# power-shield-v210.net
KiCad netlist of a schematic drawn in EAGLE
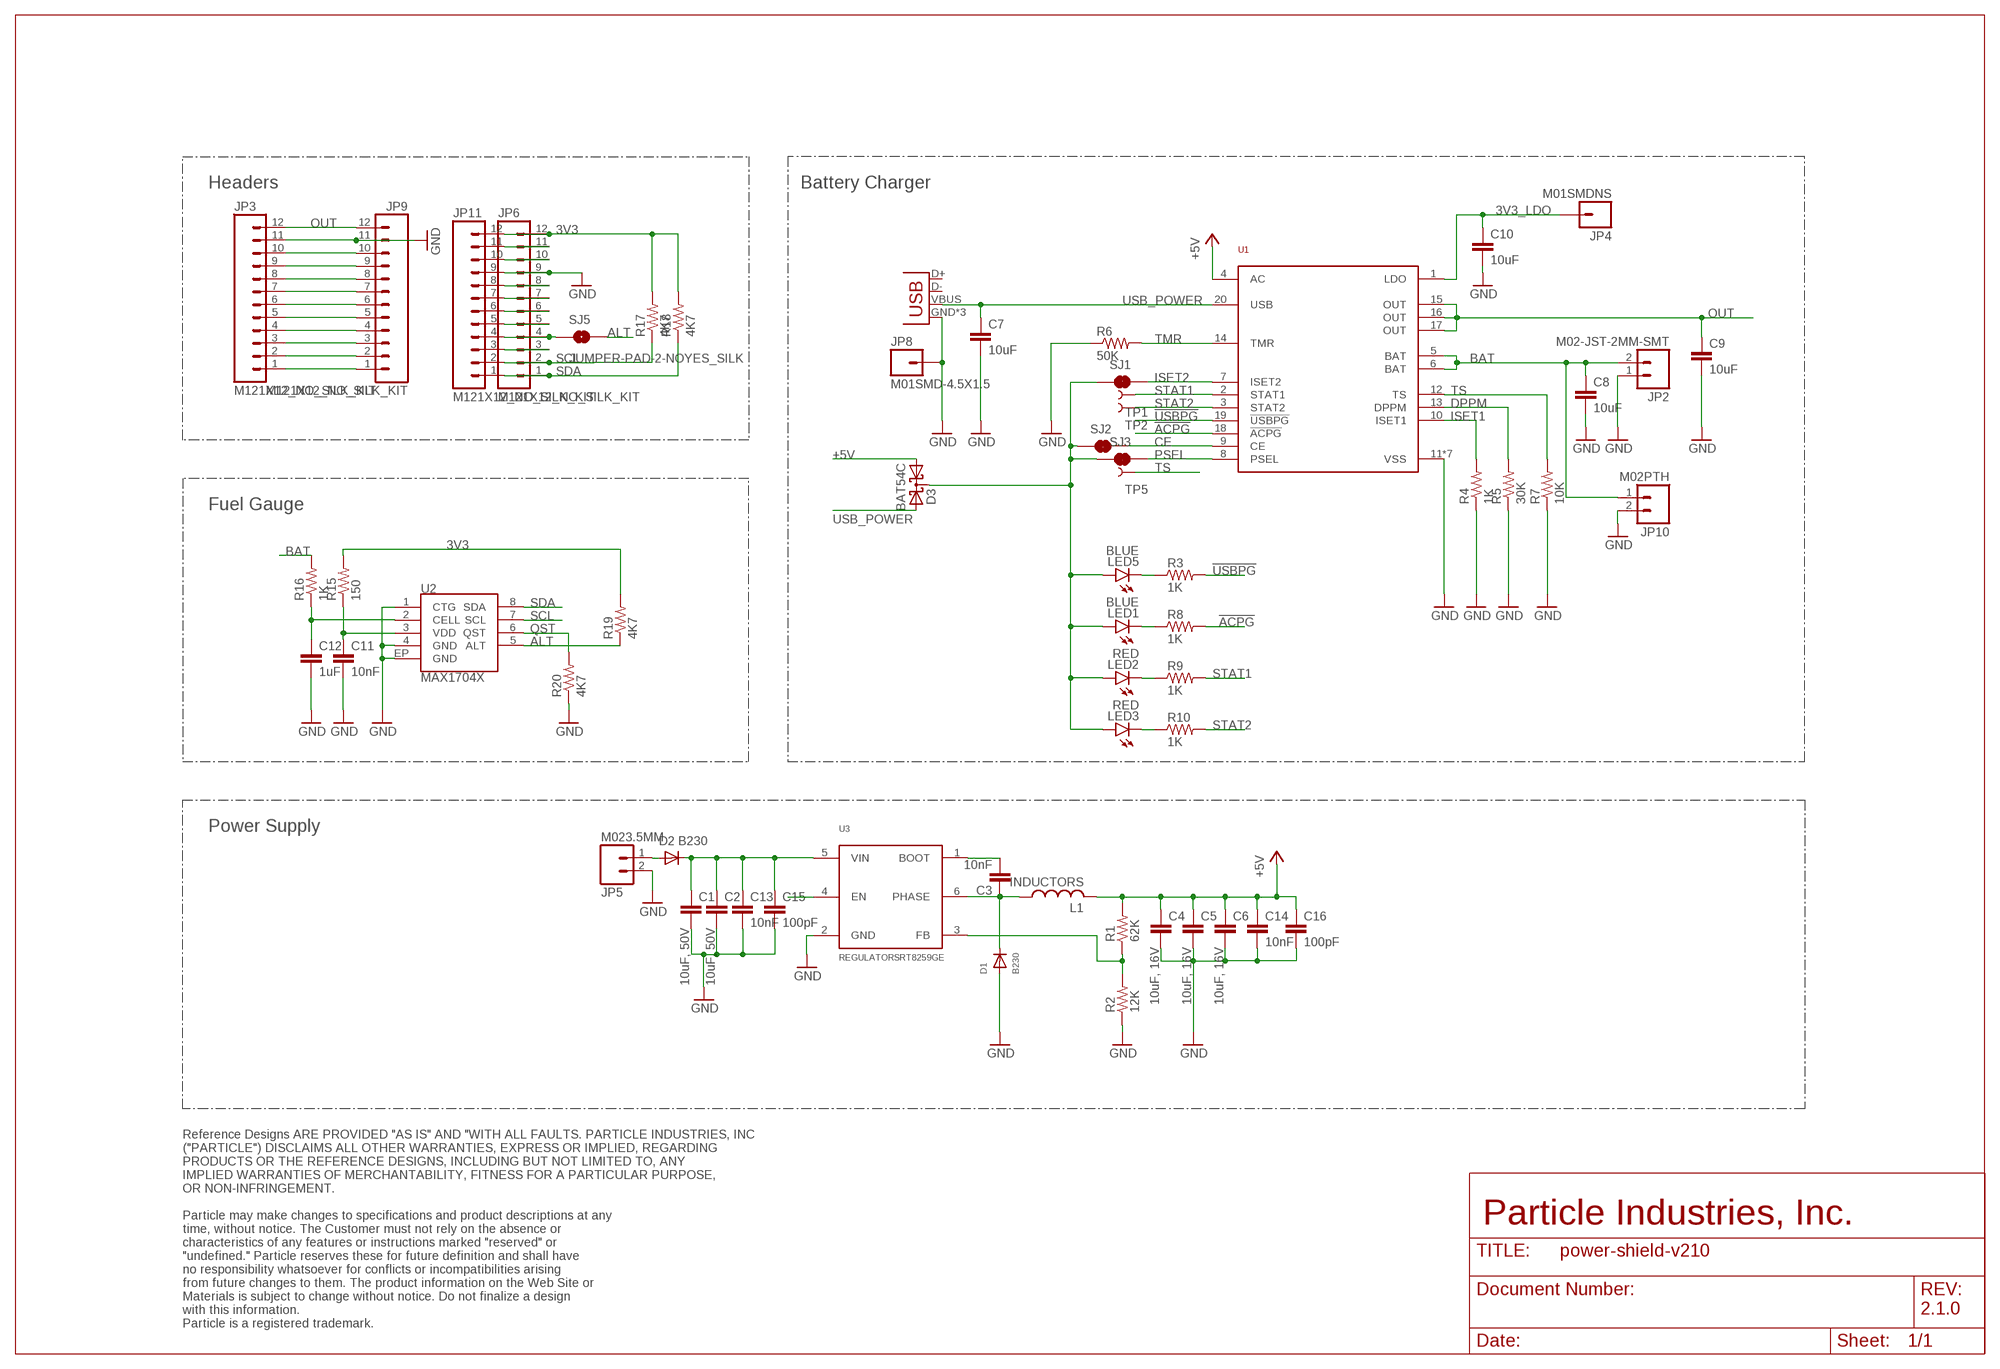
[diagram p0: schematic, sheet 1]

(export (version "E")
  (design (tool "Eeschema 10.0.6"))
  (components
    (comp (ref "C1")
      (value "10uF, 50V")
      (footprint "eagle-import:1206")
      (libsource (lib "eagle-import") (part "CAP1206"))
    )
    (comp (ref "C2")
      (value "10uF, 50V")
      (footprint "eagle-import:1206")
      (libsource (lib "eagle-import") (part "CAP1206"))
    )
    (comp (ref "C3")
      (value "10nF")
      (footprint "eagle-import:0402-CAP")
      (libsource (lib "eagle-import") (part "CAP0402-CAP"))
    )
    (comp (ref "C4")
      (value "10uF, 16V")
      (footprint "eagle-import:1206")
      (libsource (lib "eagle-import") (part "CAP1206"))
    )
    (comp (ref "C5")
      (value "10uF, 16V")
      (footprint "eagle-import:1206")
      (libsource (lib "eagle-import") (part "CAP1206"))
    )
    (comp (ref "C6")
      (value "10uF, 16V")
      (footprint "eagle-import:1206")
      (libsource (lib "eagle-import") (part "CAP1206"))
    )
    (comp (ref "C7")
      (value "10uF")
      (footprint "eagle-import:0603-CAP")
      (libsource (lib "eagle-import") (part "CAP0603-CAP"))
    )
    (comp (ref "C8")
      (value "10uF")
      (footprint "eagle-import:0603-CAP")
      (libsource (lib "eagle-import") (part "CAP0603-CAP"))
    )
    (comp (ref "C9")
      (value "10uF")
      (footprint "eagle-import:0603-CAP")
      (libsource (lib "eagle-import") (part "CAP0603-CAP"))
    )
    (comp (ref "C10")
      (value "10uF")
      (footprint "eagle-import:0603-CAP")
      (libsource (lib "eagle-import") (part "CAP0603-CAP"))
    )
    (comp (ref "C11")
      (value "10nF")
      (footprint "eagle-import:0402-CAP")
      (libsource (lib "eagle-import") (part "CAP0402-CAP"))
    )
    (comp (ref "C12")
      (value "1uF")
      (footprint "eagle-import:0402-CAP")
      (libsource (lib "eagle-import") (part "CAP0402-CAP"))
    )
    (comp (ref "C13")
      (value "10nF")
      (footprint "eagle-import:0402-CAP")
      (libsource (lib "eagle-import") (part "CAP0402-CAP"))
    )
    (comp (ref "C14")
      (value "10nF")
      (footprint "eagle-import:0402-CAP")
      (libsource (lib "eagle-import") (part "CAP0402-CAP"))
    )
    (comp (ref "C15")
      (value "100pF")
      (footprint "eagle-import:0402-CAP")
      (libsource (lib "eagle-import") (part "CAP0402-CAP"))
    )
    (comp (ref "C16")
      (value "100pF")
      (footprint "eagle-import:0402-CAP")
      (libsource (lib "eagle-import") (part "CAP0402-CAP"))
    )
    (comp (ref "D1")
      (value "B230")
      (footprint "eagle-import:SMADIODE")
      (libsource (lib "eagle-import") (part "DIODESMA"))
    )
    (comp (ref "D2")
      (value "B230")
      (footprint "eagle-import:SMADIODE")
      (libsource (lib "eagle-import") (part "DIODESMA"))
    )
    (comp (ref "D3")
      (value "BAT54C")
      (footprint "eagle-import:SOT23")
      (libsource (lib "eagle-import") (part "BAT54C"))
    )
    (comp (ref "JP1")
      (value "USBUSB-MICROB-SLOT-HOLE")
      (footprint "eagle-import:USB-MICROB-SLOT-HOLE")
      (libsource (lib "eagle-import") (part "USBUSB-MICROB-SLOT-HOLE"))
    )
    (comp (ref "JP2")
      (value "M02-JST-2MM-SMT")
      (footprint "eagle-import:JST-2-SMD")
      (libsource (lib "eagle-import") (part "M02-JST-2MM-SMT"))
    )
    (comp (ref "JP3")
      (value "M121X12_NO_SILK_KIT")
      (footprint "eagle-import:1X12_NO_SILK_KIT")
      (libsource (lib "eagle-import") (part "M121X12_NO_SILK_KIT"))
    )
    (comp (ref "JP4")
      (value "M01SMDNS")
      (footprint "eagle-import:1X01NS")
      (libsource (lib "eagle-import") (part "M01SMDNS"))
    )
    (comp (ref "JP5")
      (value "M023.5MM")
      (footprint "eagle-import:SCREWTERMINAL-3.5MM-2")
      (libsource (lib "eagle-import") (part "M023.5MM"))
    )
    (comp (ref "JP6")
      (value "M121X12_NO_SILK_KIT")
      (footprint "eagle-import:1X12_NO_SILK_KIT")
      (libsource (lib "eagle-import") (part "M121X12_NO_SILK_KIT"))
    )
    (comp (ref "JP8")
      (value "M01SMD-4.5X1.5")
      (footprint "eagle-import:PAD-1.5X4.5")
      (libsource (lib "eagle-import") (part "M01SMD-4.5X1.5"))
    )
    (comp (ref "JP9")
      (value "M121X12_NO_SILK_KIT")
      (footprint "eagle-import:1X12_NO_SILK_KIT")
      (libsource (lib "eagle-import") (part "M121X12_NO_SILK_KIT"))
    )
    (comp (ref "JP10")
      (value "M02PTH")
      (footprint "eagle-import:1X02")
      (libsource (lib "eagle-import") (part "M02PTH"))
    )
    (comp (ref "JP11")
      (value "M121X12_NO_SILK_KIT")
      (footprint "eagle-import:1X12_NO_SILK_KIT")
      (libsource (lib "eagle-import") (part "M121X12_NO_SILK_KIT"))
    )
    (comp (ref "L1")
      (value "INDUCTORS")
      (footprint "eagle-import:NR8040T6R8N")
      (libsource (lib "eagle-import") (part "INDUCTORS"))
    )
    (comp (ref "LED1")
      (value "BLUE")
      (footprint "eagle-import:LED-0603")
      (libsource (lib "eagle-import") (part "LED0603"))
    )
    (comp (ref "LED2")
      (value "RED")
      (footprint "eagle-import:LED-0603")
      (libsource (lib "eagle-import") (part "LED0603"))
    )
    (comp (ref "LED3")
      (value "RED")
      (footprint "eagle-import:LED-0603")
      (libsource (lib "eagle-import") (part "LED0603"))
    )
    (comp (ref "LED5")
      (value "BLUE")
      (footprint "eagle-import:LED-0603")
      (libsource (lib "eagle-import") (part "LED0603"))
    )
    (comp (ref "R1")
      (value "62K")
      (footprint "eagle-import:0603-RES")
      (libsource (lib "eagle-import") (part "RESISTOR0603-RES"))
    )
    (comp (ref "R2")
      (value "12K")
      (footprint "eagle-import:0603-RES")
      (libsource (lib "eagle-import") (part "RESISTOR0603-RES"))
    )
    (comp (ref "R3")
      (value "1K")
      (footprint "eagle-import:0402-RES")
      (libsource (lib "eagle-import") (part "RESISTOR0402-RES"))
    )
    (comp (ref "R4")
      (value "1K")
      (footprint "eagle-import:0402-RES")
      (libsource (lib "eagle-import") (part "RESISTOR0402-RES"))
    )
    (comp (ref "R5")
      (value "30K")
      (footprint "eagle-import:0402-RES")
      (libsource (lib "eagle-import") (part "RESISTOR0402-RES"))
    )
    (comp (ref "R6")
      (value "50K")
      (footprint "eagle-import:0402-RES")
      (libsource (lib "eagle-import") (part "RESISTOR0402-RES"))
    )
    (comp (ref "R7")
      (value "10K")
      (footprint "eagle-import:0402-RES")
      (libsource (lib "eagle-import") (part "RESISTOR0402-RES"))
    )
    (comp (ref "R8")
      (value "1K")
      (footprint "eagle-import:0402-RES")
      (libsource (lib "eagle-import") (part "RESISTOR0402-RES"))
    )
    (comp (ref "R9")
      (value "1K")
      (footprint "eagle-import:0402-RES")
      (libsource (lib "eagle-import") (part "RESISTOR0402-RES"))
    )
    (comp (ref "R10")
      (value "1K")
      (footprint "eagle-import:0402-RES")
      (libsource (lib "eagle-import") (part "RESISTOR0402-RES"))
    )
    (comp (ref "R15")
      (value "150")
      (footprint "eagle-import:0603-RES")
      (libsource (lib "eagle-import") (part "RESISTOR0603-RES"))
    )
    (comp (ref "R16")
      (value "1K")
      (footprint "eagle-import:0603-RES")
      (libsource (lib "eagle-import") (part "RESISTOR0603-RES"))
    )
    (comp (ref "R17")
      (value "4K7")
      (footprint "eagle-import:0402-RES")
      (libsource (lib "eagle-import") (part "RESISTOR0402-RES"))
    )
    (comp (ref "R18")
      (value "4K7")
      (footprint "eagle-import:0402-RES")
      (libsource (lib "eagle-import") (part "RESISTOR0402-RES"))
    )
    (comp (ref "R19")
      (value "4K7")
      (footprint "eagle-import:0402-RES")
      (libsource (lib "eagle-import") (part "RESISTOR0402-RES"))
    )
    (comp (ref "R20")
      (value "4K7")
      (footprint "eagle-import:0402-RES")
      (libsource (lib "eagle-import") (part "RESISTOR0402-RES"))
    )
    (comp (ref "SJ1")
      (value "JUMPER-PAD-2-NC_BY_TRACE")
      (footprint "eagle-import:PAD-JUMPER-2-NC_BY_TRACE_YES_SILK")
      (libsource (lib "eagle-import") (part "JUMPER-PAD-2-NC_BY_TRACE"))
    )
    (comp (ref "SJ2")
      (value "JUMPER-PAD-2-NC_BY_TRACE")
      (footprint "eagle-import:PAD-JUMPER-2-NC_BY_TRACE_YES_SILK")
      (libsource (lib "eagle-import") (part "JUMPER-PAD-2-NC_BY_TRACE"))
    )
    (comp (ref "SJ3")
      (value "JUMPER-PAD-2-NC_BY_TRACE")
      (footprint "eagle-import:PAD-JUMPER-2-NC_BY_TRACE_YES_SILK")
      (libsource (lib "eagle-import") (part "JUMPER-PAD-2-NC_BY_TRACE"))
    )
    (comp (ref "SJ5")
      (value "JUMPER-PAD-2-NOYES_SILK")
      (footprint "eagle-import:PAD-JUMPER-2-NO_YES_SILK")
      (libsource (lib "eagle-import") (part "JUMPER-PAD-2-NOYES_SILK"))
    )
    (comp (ref "TP1")
      (value "TEST-POINT3")
      (footprint "eagle-import:PAD.03X.03")
      (libsource (lib "eagle-import") (part "TEST-POINT3"))
    )
    (comp (ref "TP2")
      (value "TEST-POINT3")
      (footprint "eagle-import:PAD.03X.03")
      (libsource (lib "eagle-import") (part "TEST-POINT3"))
    )
    (comp (ref "TP5")
      (value "TEST-POINT3")
      (footprint "eagle-import:PAD.03X.03")
      (libsource (lib "eagle-import") (part "TEST-POINT3"))
    )
    (comp (ref "U1")
      (value "BQ24030BQ24030")
      (footprint "eagle-import:R-PVQFN-N20")
      (libsource (lib "eagle-import") (part "BQ24030BQ24030"))
    )
    (comp (ref "U2")
      (value "MAX1704X")
      (footprint "eagle-import:TDFN-8")
      (libsource (lib "eagle-import") (part "MAX1704X"))
    )
    (comp (ref "U3")
      (value "REGULATORSRT8259GE")
      (footprint "eagle-import:SOT23-6")
      (libsource (lib "eagle-import") (part "REGULATORSRT8259GE"))
    )
  )
  (nets
    (net (code "1") (name "+5V") (class "Default")
      (node (ref "C14") (pin "1") (pinfunction "1_1") (pintype "passive"))
      (node (ref "C16") (pin "1") (pinfunction "1_1") (pintype "passive"))
      (node (ref "C4") (pin "1") (pinfunction "1_1") (pintype "passive"))
      (node (ref "C5") (pin "1") (pinfunction "1_1") (pintype "passive"))
      (node (ref "C6") (pin "1") (pinfunction "1_1") (pintype "passive"))
      (node (ref "D3") (pin "1") (pinfunction "A1_1") (pintype "passive"))
      (node (ref "L1") (pin "P$2") (pinfunction "2_P$2") (pintype "passive"))
      (node (ref "R1") (pin "2") (pinfunction "2_2") (pintype "passive"))
      (node (ref "U1") (pin "4") (pinfunction "AC_4") (pintype "power_in"))
    )
    (net (code "2") (name "/3V3") (class "Default")
      (node (ref "JP11") (pin "12") (pinfunction "12_12") (pintype "passive"))
      (node (ref "JP6") (pin "12") (pinfunction "12_12") (pintype "passive"))
      (node (ref "R15") (pin "2") (pinfunction "2_2") (pintype "passive"))
      (node (ref "R17") (pin "2") (pinfunction "2_2") (pintype "passive"))
      (node (ref "R18") (pin "2") (pinfunction "2_2") (pintype "passive"))
      (node (ref "R19") (pin "2") (pinfunction "2_2") (pintype "passive"))
    )
    (net (code "3") (name "/3V3_LDO") (class "Default")
      (node (ref "C10") (pin "1") (pinfunction "1_1") (pintype "passive"))
      (node (ref "JP4") (pin "1") (pinfunction "1_1") (pintype "passive"))
      (node (ref "U1") (pin "1") (pinfunction "LDO_1") (pintype "output"))
    )
    (net (code "4") (name "/ALT") (class "Default")
      (node (ref "R19") (pin "1") (pinfunction "1_1") (pintype "passive"))
      (node (ref "SJ5") (pin "2") (pinfunction "2_2") (pintype "passive"))
      (node (ref "U2") (pin "5") (pinfunction "ALT_5") (pintype "bidirectional"))
    )
    (net (code "5") (name "/BAT") (class "Default")
      (node (ref "C8") (pin "1") (pinfunction "1_1") (pintype "passive"))
      (node (ref "JP10") (pin "1") (pinfunction "1_1") (pintype "passive"))
      (node (ref "JP2") (pin "2") (pinfunction "1_2") (pintype "passive"))
      (node (ref "R16") (pin "2") (pinfunction "2_2") (pintype "passive"))
      (node (ref "U1") (pin "5") (pinfunction "BAT_5") (pintype "output"))
      (node (ref "U1") (pin "6") (pinfunction "BAT_6") (pintype "output"))
    )
    (net (code "6") (name "/CE") (class "Default")
      (node (ref "SJ2") (pin "2") (pinfunction "2_2") (pintype "passive"))
      (node (ref "U1") (pin "9") (pinfunction "CE_9") (pintype "input"))
    )
    (net (code "7") (name "/DPPM") (class "Default")
      (node (ref "R5") (pin "2") (pinfunction "2_2") (pintype "passive"))
      (node (ref "U1") (pin "13") (pinfunction "DPPM_13") (pintype "bidirectional"))
    )
    (net (code "8") (name "/ISET1") (class "Default")
      (node (ref "R4") (pin "2") (pinfunction "2_2") (pintype "passive"))
      (node (ref "U1") (pin "10") (pinfunction "ISET1_10") (pintype "bidirectional"))
    )
    (net (code "9") (name "/ISET2") (class "Default")
      (node (ref "SJ1") (pin "2") (pinfunction "2_2") (pintype "passive"))
      (node (ref "U1") (pin "7") (pinfunction "ISET2_7") (pintype "input"))
    )
    (net (code "10") (name "/OUT") (class "Default")
      (node (ref "C9") (pin "1") (pinfunction "1_1") (pintype "passive"))
      (node (ref "JP3") (pin "12") (pinfunction "12_12") (pintype "passive"))
      (node (ref "JP9") (pin "12") (pinfunction "12_12") (pintype "passive"))
      (node (ref "U1") (pin "15") (pinfunction "OUT_15") (pintype "output"))
      (node (ref "U1") (pin "16") (pinfunction "OUT_16") (pintype "output"))
      (node (ref "U1") (pin "17") (pinfunction "OUT_17") (pintype "output"))
    )
    (net (code "11") (name "/PSEL") (class "Default")
      (node (ref "SJ3") (pin "2") (pinfunction "2_2") (pintype "passive"))
      (node (ref "U1") (pin "8") (pinfunction "PSEL_8") (pintype "input"))
    )
    (net (code "12") (name "/QST") (class "Default")
      (node (ref "R20") (pin "2") (pinfunction "2_2") (pintype "passive"))
      (node (ref "U2") (pin "6") (pinfunction "QST_6") (pintype "bidirectional"))
    )
    (net (code "13") (name "/SCL") (class "Default")
      (node (ref "JP11") (pin "2") (pinfunction "2_2") (pintype "passive"))
      (node (ref "JP6") (pin "2") (pinfunction "2_2") (pintype "passive"))
      (node (ref "R17") (pin "1") (pinfunction "1_1") (pintype "passive"))
      (node (ref "U2") (pin "7") (pinfunction "SCL_7") (pintype "bidirectional"))
    )
    (net (code "14") (name "/SDA") (class "Default")
      (node (ref "JP11") (pin "1") (pinfunction "1_1") (pintype "passive"))
      (node (ref "JP6") (pin "1") (pinfunction "1_1") (pintype "passive"))
      (node (ref "R18") (pin "1") (pinfunction "1_1") (pintype "passive"))
      (node (ref "U2") (pin "8") (pinfunction "SDA_8") (pintype "bidirectional"))
    )
    (net (code "15") (name "/STAT1") (class "Default")
      (node (ref "R9") (pin "2") (pinfunction "2_2") (pintype "passive"))
      (node (ref "TP1") (pin "P$1") (pinfunction "1_P$1") (pintype "bidirectional"))
      (node (ref "U1") (pin "2") (pinfunction "STAT1_2") (pintype "output"))
    )
    (net (code "16") (name "/STAT2") (class "Default")
      (node (ref "R10") (pin "2") (pinfunction "2_2") (pintype "passive"))
      (node (ref "TP2") (pin "P$1") (pinfunction "1_P$1") (pintype "bidirectional"))
      (node (ref "U1") (pin "3") (pinfunction "STAT2_3") (pintype "output"))
    )
    (net (code "17") (name "/TMR") (class "Default")
      (node (ref "R6") (pin "2") (pinfunction "2_2") (pintype "passive"))
      (node (ref "U1") (pin "14") (pinfunction "TMR_14") (pintype "power_in"))
    )
    (net (code "18") (name "/TS") (class "Default")
      (node (ref "R7") (pin "2") (pinfunction "2_2") (pintype "passive"))
      (node (ref "TP5") (pin "P$1") (pinfunction "1_P$1") (pintype "bidirectional"))
      (node (ref "U1") (pin "12") (pinfunction "TS_12") (pintype "bidirectional"))
    )
    (net (code "19") (name "/USB_POWER") (class "Default")
      (node (ref "C7") (pin "1") (pinfunction "1_1") (pintype "passive"))
      (node (ref "D3") (pin "2") (pinfunction "A2_2") (pintype "passive"))
      (node (ref "JP1") (pin "VBUS") (pinfunction "VBUS_VBUS") (pintype "bidirectional"))
      (node (ref "U1") (pin "20") (pinfunction "USB_20") (pintype "power_in"))
    )
    (net (code "20") (name "/~{ACPG}") (class "Default")
      (node (ref "R8") (pin "2") (pinfunction "2_2") (pintype "passive"))
      (node (ref "U1") (pin "18") (pinfunction "~{ACPG}_18") (pintype "input"))
    )
    (net (code "21") (name "/~{USBPG}") (class "Default")
      (node (ref "R3") (pin "2") (pinfunction "2_2") (pintype "passive"))
      (node (ref "U1") (pin "19") (pinfunction "~{USBPG}_19") (pintype "input"))
    )
    (net (code "22") (name "GND") (class "Default")
      (node (ref "C1") (pin "2") (pinfunction "2_2") (pintype "passive"))
      (node (ref "C10") (pin "2") (pinfunction "2_2") (pintype "passive"))
      (node (ref "C11") (pin "2") (pinfunction "2_2") (pintype "passive"))
      (node (ref "C12") (pin "2") (pinfunction "2_2") (pintype "passive"))
      (node (ref "C13") (pin "2") (pinfunction "2_2") (pintype "passive"))
      (node (ref "C14") (pin "2") (pinfunction "2_2") (pintype "passive"))
      (node (ref "C15") (pin "2") (pinfunction "2_2") (pintype "passive"))
      (node (ref "C16") (pin "2") (pinfunction "2_2") (pintype "passive"))
      (node (ref "C2") (pin "2") (pinfunction "2_2") (pintype "passive"))
      (node (ref "C4") (pin "2") (pinfunction "2_2") (pintype "passive"))
      (node (ref "C5") (pin "2") (pinfunction "2_2") (pintype "passive"))
      (node (ref "C6") (pin "2") (pinfunction "2_2") (pintype "passive"))
      (node (ref "C7") (pin "2") (pinfunction "2_2") (pintype "passive"))
      (node (ref "C8") (pin "2") (pinfunction "2_2") (pintype "passive"))
      (node (ref "C9") (pin "2") (pinfunction "2_2") (pintype "passive"))
      (node (ref "D1") (pin "A") (pinfunction "A_A") (pintype "passive"))
      (node (ref "JP1") (pin "GND") (pinfunction "GND_GND") (pintype "bidirectional"))
      (node (ref "JP1") (pin "MT1") (pinfunction "GND_MT1") (pintype "bidirectional"))
      (node (ref "JP1") (pin "MT2") (pinfunction "GND_MT2") (pintype "bidirectional"))
      (node (ref "JP10") (pin "2") (pinfunction "2_2") (pintype "passive"))
      (node (ref "JP11") (pin "9") (pinfunction "9_9") (pintype "passive"))
      (node (ref "JP2") (pin "1") (pinfunction "2_1") (pintype "passive"))
      (node (ref "JP3") (pin "11") (pinfunction "11_11") (pintype "passive"))
      (node (ref "JP5") (pin "2") (pinfunction "2_2") (pintype "passive"))
      (node (ref "JP6") (pin "9") (pinfunction "9_9") (pintype "passive"))
      (node (ref "JP8") (pin "P$1") (pinfunction "1_P$1") (pintype "passive"))
      (node (ref "JP9") (pin "11") (pinfunction "11_11") (pintype "passive"))
      (node (ref "R2") (pin "1") (pinfunction "1_1") (pintype "passive"))
      (node (ref "R20") (pin "1") (pinfunction "1_1") (pintype "passive"))
      (node (ref "R4") (pin "1") (pinfunction "1_1") (pintype "passive"))
      (node (ref "R5") (pin "1") (pinfunction "1_1") (pintype "passive"))
      (node (ref "R6") (pin "1") (pinfunction "1_1") (pintype "passive"))
      (node (ref "R7") (pin "1") (pinfunction "1_1") (pintype "passive"))
      (node (ref "U1") (pin "11") (pinfunction "VSS_11") (pintype "power_in"))
      (node (ref "U1") (pin "21") (pinfunction "VSS_21") (pintype "power_in"))
      (node (ref "U1") (pin "22") (pinfunction "VSS_22") (pintype "power_in"))
      (node (ref "U1") (pin "23") (pinfunction "VSS_23") (pintype "power_in"))
      (node (ref "U1") (pin "24") (pinfunction "VSS_24") (pintype "power_in"))
      (node (ref "U1") (pin "25") (pinfunction "VSS_25") (pintype "power_in"))
      (node (ref "U1") (pin "26") (pinfunction "VSS_26") (pintype "power_in"))
      (node (ref "U2") (pin "1") (pinfunction "CTG_1") (pintype "bidirectional"))
      (node (ref "U2") (pin "4") (pinfunction "GND_4") (pintype "bidirectional"))
      (node (ref "U2") (pin "EP") (pinfunction "GND_EP") (pintype "bidirectional"))
      (node (ref "U3") (pin "2") (pinfunction "GND_2") (pintype "bidirectional"))
    )
    (net (code "23") (name "Net-(D2-PadA)") (class "Default")
      (node (ref "D2") (pin "A") (pinfunction "A_A") (pintype "passive"))
      (node (ref "JP5") (pin "1") (pinfunction "1_1") (pintype "passive"))
    )
    (net (code "24") (name "Net-(D3-CC)") (class "Default")
      (node (ref "D3") (pin "3") (pinfunction "CC_3") (pintype "passive"))
      (node (ref "LED1") (pin "A") (pinfunction "A_A") (pintype "passive"))
      (node (ref "LED2") (pin "A") (pinfunction "A_A") (pintype "passive"))
      (node (ref "LED3") (pin "A") (pinfunction "A_A") (pintype "passive"))
      (node (ref "LED5") (pin "A") (pinfunction "A_A") (pintype "passive"))
      (node (ref "SJ1") (pin "1") (pinfunction "1_1") (pintype "passive"))
      (node (ref "SJ2") (pin "1") (pinfunction "1_1") (pintype "passive"))
      (node (ref "SJ3") (pin "1") (pinfunction "1_1") (pintype "passive"))
    )
    (net (code "25") (name "Net-(JP3-Pad1)") (class "Default")
      (node (ref "JP3") (pin "1") (pinfunction "1_1") (pintype "passive"))
      (node (ref "JP9") (pin "1") (pinfunction "1_1") (pintype "passive"))
    )
    (net (code "26") (name "Net-(JP3-Pad2)") (class "Default")
      (node (ref "JP3") (pin "2") (pinfunction "2_2") (pintype "passive"))
      (node (ref "JP9") (pin "2") (pinfunction "2_2") (pintype "passive"))
    )
    (net (code "27") (name "Net-(JP3-Pad3)") (class "Default")
      (node (ref "JP3") (pin "3") (pinfunction "3_3") (pintype "passive"))
      (node (ref "JP9") (pin "3") (pinfunction "3_3") (pintype "passive"))
    )
    (net (code "28") (name "Net-(JP3-Pad4)") (class "Default")
      (node (ref "JP3") (pin "4") (pinfunction "4_4") (pintype "passive"))
      (node (ref "JP9") (pin "4") (pinfunction "4_4") (pintype "passive"))
    )
    (net (code "29") (name "Net-(JP3-Pad5)") (class "Default")
      (node (ref "JP3") (pin "5") (pinfunction "5_5") (pintype "passive"))
      (node (ref "JP9") (pin "5") (pinfunction "5_5") (pintype "passive"))
    )
    (net (code "30") (name "Net-(JP3-Pad6)") (class "Default")
      (node (ref "JP3") (pin "6") (pinfunction "6_6") (pintype "passive"))
      (node (ref "JP9") (pin "6") (pinfunction "6_6") (pintype "passive"))
    )
    (net (code "31") (name "Net-(JP3-Pad7)") (class "Default")
      (node (ref "JP3") (pin "7") (pinfunction "7_7") (pintype "passive"))
      (node (ref "JP9") (pin "7") (pinfunction "7_7") (pintype "passive"))
    )
    (net (code "32") (name "Net-(JP3-Pad8)") (class "Default")
      (node (ref "JP3") (pin "8") (pinfunction "8_8") (pintype "passive"))
      (node (ref "JP9") (pin "8") (pinfunction "8_8") (pintype "passive"))
    )
    (net (code "33") (name "Net-(JP3-Pad9)") (class "Default")
      (node (ref "JP3") (pin "9") (pinfunction "9_9") (pintype "passive"))
      (node (ref "JP9") (pin "9") (pinfunction "9_9") (pintype "passive"))
    )
    (net (code "34") (name "Net-(JP3-Pad10)") (class "Default")
      (node (ref "JP3") (pin "10") (pinfunction "10_10") (pintype "passive"))
      (node (ref "JP9") (pin "10") (pinfunction "10_10") (pintype "passive"))
    )
    (net (code "35") (name "Net-(JP11-Pad3)") (class "Default")
      (node (ref "JP11") (pin "3") (pinfunction "3_3") (pintype "passive"))
      (node (ref "JP6") (pin "3") (pinfunction "3_3") (pintype "passive"))
    )
    (net (code "36") (name "Net-(JP11-Pad4)") (class "Default")
      (node (ref "JP11") (pin "4") (pinfunction "4_4") (pintype "passive"))
      (node (ref "JP6") (pin "4") (pinfunction "4_4") (pintype "passive"))
      (node (ref "SJ5") (pin "1") (pinfunction "1_1") (pintype "passive"))
    )
    (net (code "37") (name "Net-(JP11-Pad5)") (class "Default")
      (node (ref "JP11") (pin "5") (pinfunction "5_5") (pintype "passive"))
      (node (ref "JP6") (pin "5") (pinfunction "5_5") (pintype "passive"))
    )
    (net (code "38") (name "Net-(JP11-Pad6)") (class "Default")
      (node (ref "JP11") (pin "6") (pinfunction "6_6") (pintype "passive"))
      (node (ref "JP6") (pin "6") (pinfunction "6_6") (pintype "passive"))
    )
    (net (code "39") (name "Net-(JP11-Pad7)") (class "Default")
      (node (ref "JP11") (pin "7") (pinfunction "7_7") (pintype "passive"))
      (node (ref "JP6") (pin "7") (pinfunction "7_7") (pintype "passive"))
    )
    (net (code "40") (name "Net-(JP11-Pad8)") (class "Default")
      (node (ref "JP11") (pin "8") (pinfunction "8_8") (pintype "passive"))
      (node (ref "JP6") (pin "8") (pinfunction "8_8") (pintype "passive"))
    )
    (net (code "41") (name "Net-(JP11-Pad10)") (class "Default")
      (node (ref "JP11") (pin "10") (pinfunction "10_10") (pintype "passive"))
      (node (ref "JP6") (pin "10") (pinfunction "10_10") (pintype "passive"))
    )
    (net (code "42") (name "Net-(JP11-Pad11)") (class "Default")
      (node (ref "JP11") (pin "11") (pinfunction "11_11") (pintype "passive"))
      (node (ref "JP6") (pin "11") (pinfunction "11_11") (pintype "passive"))
    )
    (net (code "43") (name "Net-(L1-1)") (class "Default")
      (node (ref "C3") (pin "1") (pinfunction "1_1") (pintype "passive"))
      (node (ref "D1") (pin "C") (pinfunction "C_C") (pintype "passive"))
      (node (ref "L1") (pin "P$1") (pinfunction "1_P$1") (pintype "passive"))
      (node (ref "U3") (pin "6") (pinfunction "PHASE_6") (pintype "output"))
    )
    (net (code "44") (name "Net-(LED1-PadC)") (class "Default")
      (node (ref "LED1") (pin "C") (pinfunction "C_C") (pintype "passive"))
      (node (ref "R8") (pin "1") (pinfunction "1_1") (pintype "passive"))
    )
    (net (code "45") (name "Net-(LED2-PadC)") (class "Default")
      (node (ref "LED2") (pin "C") (pinfunction "C_C") (pintype "passive"))
      (node (ref "R9") (pin "1") (pinfunction "1_1") (pintype "passive"))
    )
    (net (code "46") (name "Net-(LED3-PadC)") (class "Default")
      (node (ref "LED3") (pin "C") (pinfunction "C_C") (pintype "passive"))
      (node (ref "R10") (pin "1") (pinfunction "1_1") (pintype "passive"))
    )
    (net (code "47") (name "Net-(LED5-PadC)") (class "Default")
      (node (ref "LED5") (pin "C") (pinfunction "C_C") (pintype "passive"))
      (node (ref "R3") (pin "1") (pinfunction "1_1") (pintype "passive"))
    )
    (net (code "48") (name "Net-(U2-CELL)") (class "Default")
      (node (ref "C12") (pin "1") (pinfunction "1_1") (pintype "passive"))
      (node (ref "R16") (pin "1") (pinfunction "1_1") (pintype "passive"))
      (node (ref "U2") (pin "2") (pinfunction "CELL_2") (pintype "bidirectional"))
    )
    (net (code "49") (name "Net-(U2-VDD)") (class "Default")
      (node (ref "C11") (pin "1") (pinfunction "1_1") (pintype "passive"))
      (node (ref "R15") (pin "1") (pinfunction "1_1") (pintype "passive"))
      (node (ref "U2") (pin "3") (pinfunction "VDD_3") (pintype "bidirectional"))
    )
    (net (code "50") (name "Net-(U3-BOOT)") (class "Default")
      (node (ref "C3") (pin "2") (pinfunction "2_2") (pintype "passive"))
      (node (ref "U3") (pin "1") (pinfunction "BOOT_1") (pintype "power_in"))
    )
    (net (code "51") (name "Net-(U3-FB)") (class "Default")
      (node (ref "R1") (pin "1") (pinfunction "1_1") (pintype "passive"))
      (node (ref "R2") (pin "2") (pinfunction "2_2") (pintype "passive"))
      (node (ref "U3") (pin "3") (pinfunction "FB_3") (pintype "input"))
    )
    (net (code "52") (name "Net-(U3-VIN)") (class "Default")
      (node (ref "C1") (pin "1") (pinfunction "1_1") (pintype "passive"))
      (node (ref "C13") (pin "1") (pinfunction "1_1") (pintype "passive"))
      (node (ref "C15") (pin "1") (pinfunction "1_1") (pintype "passive"))
      (node (ref "C2") (pin "1") (pinfunction "1_1") (pintype "passive"))
      (node (ref "D2") (pin "C") (pinfunction "C_C") (pintype "passive"))
      (node (ref "U3") (pin "5") (pinfunction "VIN_5") (pintype "power_in"))
    )
    (net (code "53") (name "unconnected-(JP1-PadD+)") (class "Default")
      (node (ref "JP1") (pin "D+") (pinfunction "D+_D+") (pintype "bidirectional"))
    )
    (net (code "54") (name "unconnected-(JP1-PadD-)") (class "Default")
      (node (ref "JP1") (pin "D-") (pinfunction "D-_D-") (pintype "bidirectional"))
    )
    (net (code "55") (name "unconnected-(U3-EN-Pad4)") (class "Default")
      (node (ref "U3") (pin "4") (pinfunction "EN_4") (pintype "input"))
    )
  )
)
